# 4zollPlatine.net
KiCad netlist of a schematic drawn in EAGLE
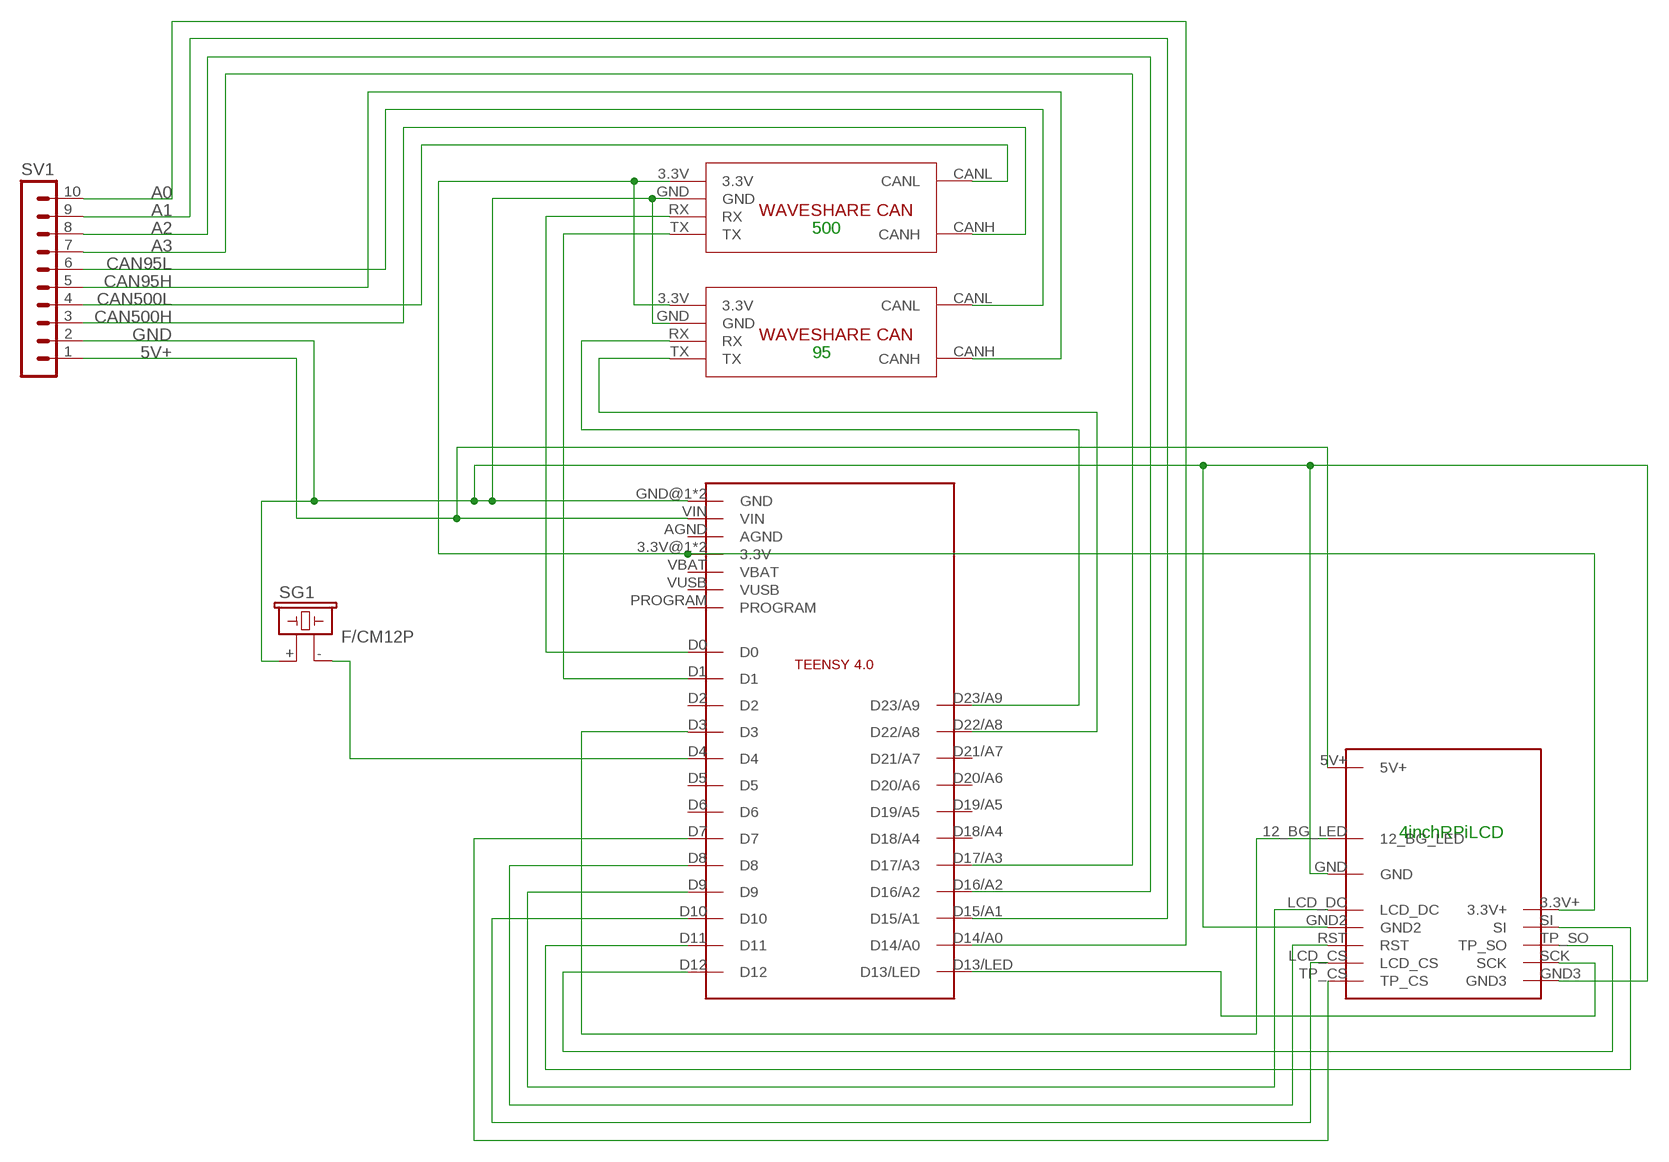
[diagram p0: schematic, sheet 1]

(export (version "E")
  (design (tool "Eeschema 10.0.6"))
  (components
    (comp (ref "95")
      (value "CAN_MODULE")
      (footprint "eagle-import:CAN_BOARD")
      (libsource (lib "eagle-import") (part "CAN_MODULE"))
    )
    (comp (ref "500")
      (value "CAN_MODULE")
      (footprint "eagle-import:CAN_BOARD")
      (libsource (lib "eagle-import") (part "CAN_MODULE"))
    )
    (comp (ref "SG1")
      (value "F/CM12P")
      (footprint "eagle-import:F_CM12P")
      (libsource (lib "eagle-import") (part "F/CM12P"))
    )
    (comp (ref "SV1")
      (value "MA10-1")
      (footprint "eagle-import:MA10-1")
      (libsource (lib "eagle-import") (part "MA10-1"))
    )
    (comp (ref "U$1")
      (value "TEENSY4.0")
      (footprint "eagle-import:TEENSY4.0")
      (libsource (lib "eagle-import") (part "TEENSY4.0"))
    )
    (comp (ref "U$2")
      (value "4INCH_RPI_LCD_DEV")
      (footprint "eagle-import:4INCH_RPI_LCD_FP")
      (libsource (lib "eagle-import") (part "4INCH_RPI_LCD_DEV"))
    )
  )
  (nets
    (net (code "1") (name "/5V+") (class "Default")
      (node (ref "SV1") (pin "1") (pinfunction "1_1") (pintype "passive"))
      (node (ref "U$1") (pin "VIN") (pinfunction "VIN_VIN") (pintype "bidirectional"))
      (node (ref "U$2") (pin "5V+") (pinfunction "5V+_5V+") (pintype "bidirectional"))
    )
    (net (code "2") (name "/A0") (class "Default")
      (node (ref "SV1") (pin "10") (pinfunction "10_10") (pintype "passive"))
      (node (ref "U$1") (pin "D14/A0") (pinfunction "D14/A0_D14/A0") (pintype "bidirectional"))
    )
    (net (code "3") (name "/A1") (class "Default")
      (node (ref "SV1") (pin "9") (pinfunction "9_9") (pintype "passive"))
      (node (ref "U$1") (pin "D15/A1") (pinfunction "D15/A1_D15/A1") (pintype "bidirectional"))
    )
    (net (code "4") (name "/A2") (class "Default")
      (node (ref "SV1") (pin "8") (pinfunction "8_8") (pintype "passive"))
      (node (ref "U$1") (pin "D16/A2") (pinfunction "D16/A2_D16/A2") (pintype "bidirectional"))
    )
    (net (code "5") (name "/A3") (class "Default")
      (node (ref "SV1") (pin "7") (pinfunction "7_7") (pintype "passive"))
      (node (ref "U$1") (pin "D17/A3") (pinfunction "D17/A3_D17/A3") (pintype "bidirectional"))
    )
    (net (code "6") (name "/CAN95H") (class "Default")
      (node (ref "95") (pin "CANH") (pinfunction "CANH_CANH") (pintype "bidirectional"))
      (node (ref "SV1") (pin "5") (pinfunction "5_5") (pintype "passive"))
    )
    (net (code "7") (name "/CAN95L") (class "Default")
      (node (ref "95") (pin "CANL") (pinfunction "CANL_CANL") (pintype "bidirectional"))
      (node (ref "SV1") (pin "6") (pinfunction "6_6") (pintype "passive"))
    )
    (net (code "8") (name "/CAN500H") (class "Default")
      (node (ref "500") (pin "CANH") (pinfunction "CANH_CANH") (pintype "bidirectional"))
      (node (ref "SV1") (pin "3") (pinfunction "3_3") (pintype "passive"))
    )
    (net (code "9") (name "/CAN500L") (class "Default")
      (node (ref "500") (pin "CANL") (pinfunction "CANL_CANL") (pintype "bidirectional"))
      (node (ref "SV1") (pin "4") (pinfunction "4_4") (pintype "passive"))
    )
    (net (code "10") (name "/GND") (class "Default")
      (node (ref "500") (pin "GND") (pinfunction "GND_GND") (pintype "power_in"))
      (node (ref "95") (pin "GND") (pinfunction "GND_GND") (pintype "power_in"))
      (node (ref "SG1") (pin "+") (pinfunction "1_+") (pintype "passive"))
      (node (ref "SV1") (pin "2") (pinfunction "2_2") (pintype "passive"))
      (node (ref "U$1") (pin "GND@1") (pinfunction "GND_GND@1") (pintype "bidirectional"))
      (node (ref "U$1") (pin "GND@2") (pinfunction "GND_GND@2") (pintype "bidirectional"))
      (node (ref "U$2") (pin "GND") (pinfunction "GND_GND") (pintype "bidirectional"))
      (node (ref "U$2") (pin "GND2") (pinfunction "GND2_GND2") (pintype "bidirectional"))
      (node (ref "U$2") (pin "GND3") (pinfunction "GND3_GND3") (pintype "bidirectional"))
    )
    (net (code "11") (name "Net-(95-PadRX)") (class "Default")
      (node (ref "95") (pin "RX") (pinfunction "RX_RX") (pintype "output"))
      (node (ref "U$1") (pin "D23/A9") (pinfunction "D23/A9_D23/A9") (pintype "bidirectional"))
    )
    (net (code "12") (name "Net-(95-PadTX)") (class "Default")
      (node (ref "95") (pin "TX") (pinfunction "TX_TX") (pintype "input"))
      (node (ref "U$1") (pin "D22/A8") (pinfunction "D22/A8_D22/A8") (pintype "bidirectional"))
    )
    (net (code "13") (name "Net-(500-Pad3.3V)") (class "Default")
      (node (ref "500") (pin "3.3V") (pinfunction "3.3V_3.3V") (pintype "power_in"))
      (node (ref "95") (pin "3.3V") (pinfunction "3.3V_3.3V") (pintype "power_in"))
      (node (ref "U$1") (pin "3.3V@1") (pinfunction "3.3V_3.3V@1") (pintype "bidirectional"))
      (node (ref "U$1") (pin "3.3V@2") (pinfunction "3.3V_3.3V@2") (pintype "bidirectional"))
      (node (ref "U$2") (pin "3.3V+") (pinfunction "3.3V+_3.3V+") (pintype "bidirectional"))
    )
    (net (code "14") (name "Net-(500-PadRX)") (class "Default")
      (node (ref "500") (pin "RX") (pinfunction "RX_RX") (pintype "output"))
      (node (ref "U$1") (pin "D0") (pinfunction "D0_D0") (pintype "bidirectional"))
    )
    (net (code "15") (name "Net-(500-PadTX)") (class "Default")
      (node (ref "500") (pin "TX") (pinfunction "TX_TX") (pintype "input"))
      (node (ref "U$1") (pin "D1") (pinfunction "D1_D1") (pintype "bidirectional"))
    )
    (net (code "16") (name "Net-(SG1-2)") (class "Default")
      (node (ref "SG1") (pin "-") (pinfunction "2_-") (pintype "passive"))
      (node (ref "U$1") (pin "D4") (pinfunction "D4_D4") (pintype "bidirectional"))
    )
    (net (code "17") (name "Net-(U$1-PadD3)") (class "Default")
      (node (ref "U$1") (pin "D3") (pinfunction "D3_D3") (pintype "bidirectional"))
      (node (ref "U$2") (pin "12_BG_LED") (pinfunction "12_BG_LED_12_BG_LED") (pintype "bidirectional"))
    )
    (net (code "18") (name "Net-(U$1-PadD7)") (class "Default")
      (node (ref "U$1") (pin "D7") (pinfunction "D7_D7") (pintype "bidirectional"))
      (node (ref "U$2") (pin "TP_CS") (pinfunction "TP_CS_TP_CS") (pintype "bidirectional"))
    )
    (net (code "19") (name "Net-(U$1-PadD8)") (class "Default")
      (node (ref "U$1") (pin "D8") (pinfunction "D8_D8") (pintype "bidirectional"))
      (node (ref "U$2") (pin "RST") (pinfunction "RST_RST") (pintype "bidirectional"))
    )
    (net (code "20") (name "Net-(U$1-PadD9)") (class "Default")
      (node (ref "U$1") (pin "D9") (pinfunction "D9_D9") (pintype "bidirectional"))
      (node (ref "U$2") (pin "LCD_DC") (pinfunction "LCD_DC_LCD_DC") (pintype "bidirectional"))
    )
    (net (code "21") (name "Net-(U$1-PadD10)") (class "Default")
      (node (ref "U$1") (pin "D10") (pinfunction "D10_D10") (pintype "bidirectional"))
      (node (ref "U$2") (pin "LCD_CS") (pinfunction "LCD_CS_LCD_CS") (pintype "bidirectional"))
    )
    (net (code "22") (name "Net-(U$1-PadD11)") (class "Default")
      (node (ref "U$1") (pin "D11") (pinfunction "D11_D11") (pintype "bidirectional"))
      (node (ref "U$2") (pin "SI") (pinfunction "SI_SI") (pintype "bidirectional"))
    )
    (net (code "23") (name "Net-(U$1-PadD12)") (class "Default")
      (node (ref "U$1") (pin "D12") (pinfunction "D12_D12") (pintype "bidirectional"))
      (node (ref "U$2") (pin "TP_SO") (pinfunction "TP_SO_TP_SO") (pintype "bidirectional"))
    )
    (net (code "24") (name "Net-(U$1-PadD13{slash}LED)") (class "Default")
      (node (ref "U$1") (pin "D13/LED") (pinfunction "D13/LED_D13/LED") (pintype "bidirectional"))
      (node (ref "U$2") (pin "SCK") (pinfunction "SCK_SCK") (pintype "bidirectional"))
    )
    (net (code "25") (name "unconnected-(U$1-PadAGND)") (class "Default")
      (node (ref "U$1") (pin "AGND") (pinfunction "AGND_AGND") (pintype "bidirectional"))
    )
    (net (code "26") (name "unconnected-(U$1-PadD2)") (class "Default")
      (node (ref "U$1") (pin "D2") (pinfunction "D2_D2") (pintype "bidirectional"))
    )
    (net (code "27") (name "unconnected-(U$1-PadD5)") (class "Default")
      (node (ref "U$1") (pin "D5") (pinfunction "D5_D5") (pintype "bidirectional"))
    )
    (net (code "28") (name "unconnected-(U$1-PadD6)") (class "Default")
      (node (ref "U$1") (pin "D6") (pinfunction "D6_D6") (pintype "bidirectional"))
    )
    (net (code "29") (name "unconnected-(U$1-PadD18{slash}A4)") (class "Default")
      (node (ref "U$1") (pin "D18/A4") (pinfunction "D18/A4_D18/A4") (pintype "bidirectional"))
    )
    (net (code "30") (name "unconnected-(U$1-PadD19{slash}A5)") (class "Default")
      (node (ref "U$1") (pin "D19/A5") (pinfunction "D19/A5_D19/A5") (pintype "bidirectional"))
    )
    (net (code "31") (name "unconnected-(U$1-PadD20{slash}A6)") (class "Default")
      (node (ref "U$1") (pin "D20/A6") (pinfunction "D20/A6_D20/A6") (pintype "bidirectional"))
    )
    (net (code "32") (name "unconnected-(U$1-PadD21{slash}A7)") (class "Default")
      (node (ref "U$1") (pin "D21/A7") (pinfunction "D21/A7_D21/A7") (pintype "bidirectional"))
    )
    (net (code "33") (name "unconnected-(U$1-PadPROGRAM)") (class "Default")
      (node (ref "U$1") (pin "PROGRAM") (pinfunction "PROGRAM_PROGRAM") (pintype "bidirectional"))
    )
    (net (code "34") (name "unconnected-(U$1-PadVBAT)") (class "Default")
      (node (ref "U$1") (pin "VBAT") (pinfunction "VBAT_VBAT") (pintype "bidirectional"))
    )
    (net (code "35") (name "unconnected-(U$1-PadVUSB)") (class "Default")
      (node (ref "U$1") (pin "VUSB") (pinfunction "VUSB_VUSB") (pintype "bidirectional"))
    )
  )
)
